# SAMD21_8X8_schematic.net
KiCad netlist of a schematic drawn in Altium Designer
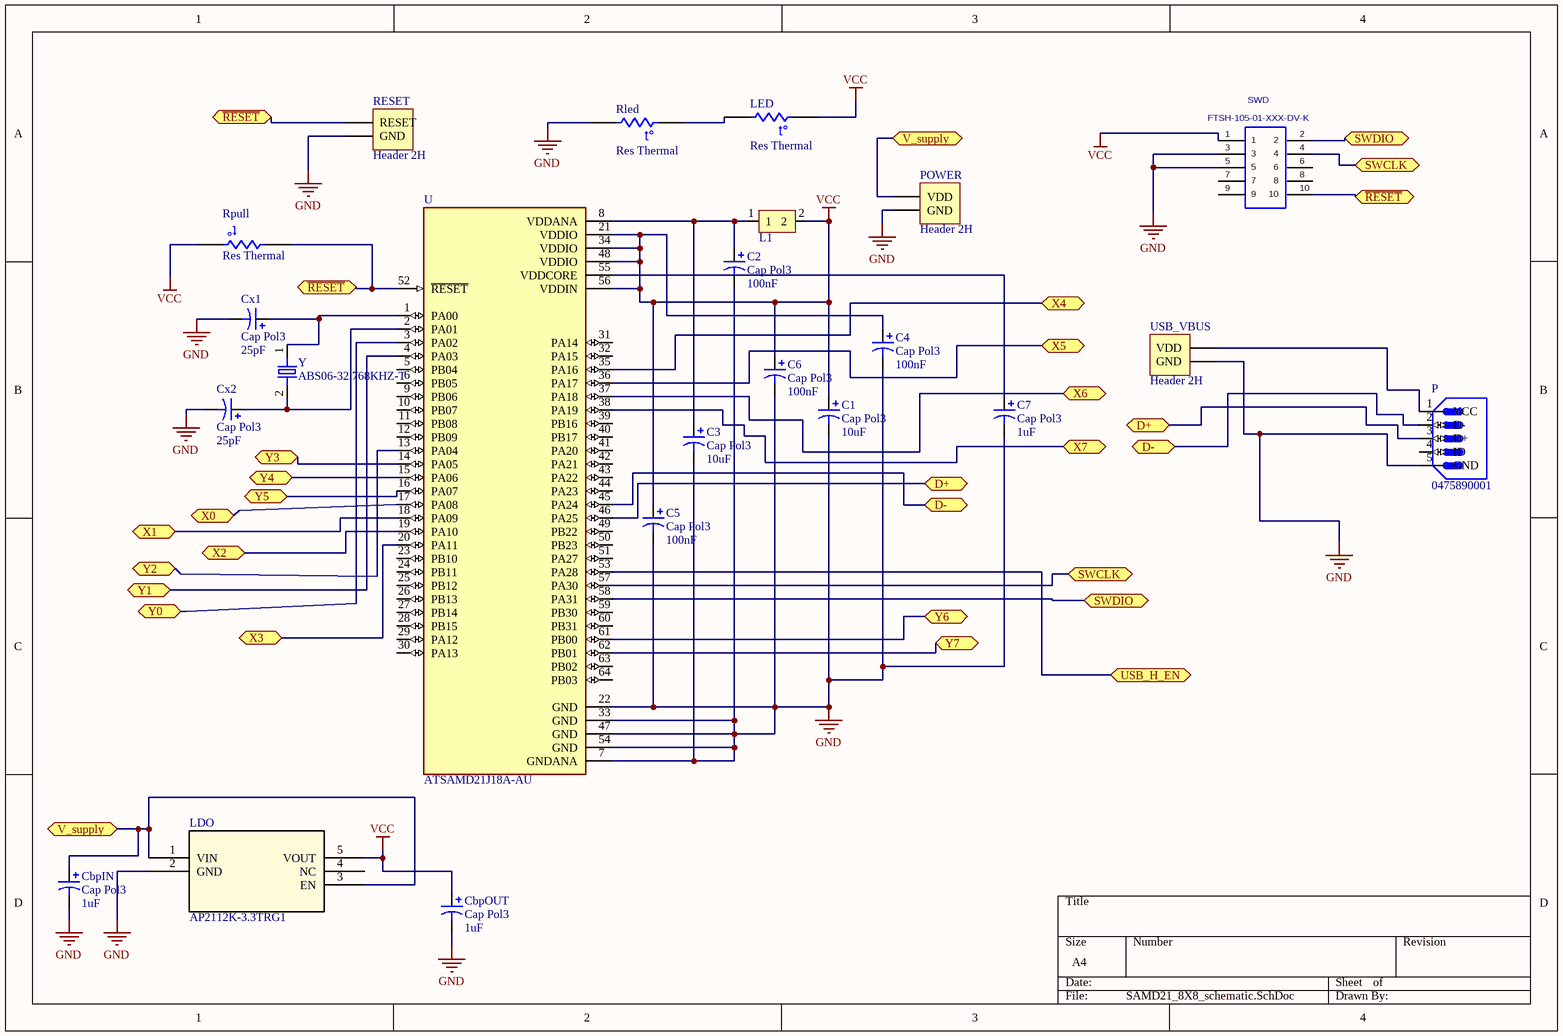
[diagram p0: SAMD21_8X8_schematic.SchDoc]

(export (version "E")
  (design (tool "Eeschema 10.0.6"))
  (components
    (comp (ref "C1")
      (value "Cap Pol3")
      (footprint "C0805")
      (description "Polarized Capacitor (Surface Mount)")
      (fields (field (name "ALTIUM_VALUE") "10uF") (field (name "PUBLISHER") "Altium Limited"))
      (libsource (lib "Miscellaneous Devices") (part "Cap Pol3"))
    )
    (comp (ref "C2")
      (value "Cap Pol3")
      (footprint "C0805")
      (description "Polarized Capacitor (Surface Mount)")
      (fields (field (name "ALTIUM_VALUE") "100nF") (field (name "PUBLISHER") "Altium Limited"))
      (libsource (lib "Miscellaneous Devices") (part "Cap Pol3"))
    )
    (comp (ref "C3")
      (value "Cap Pol3")
      (footprint "C0805")
      (description "Polarized Capacitor (Surface Mount)")
      (fields (field (name "ALTIUM_VALUE") "10uF") (field (name "PUBLISHER") "Altium Limited"))
      (libsource (lib "Miscellaneous Devices") (part "Cap Pol3"))
    )
    (comp (ref "C4")
      (value "Cap Pol3")
      (footprint "C0805")
      (description "Polarized Capacitor (Surface Mount)")
      (fields (field (name "ALTIUM_VALUE") "100nF") (field (name "PUBLISHER") "Altium Limited"))
      (libsource (lib "Miscellaneous Devices") (part "Cap Pol3"))
    )
    (comp (ref "C5")
      (value "Cap Pol3")
      (footprint "C0805")
      (description "Polarized Capacitor (Surface Mount)")
      (fields (field (name "ALTIUM_VALUE") "100nF") (field (name "PUBLISHER") "Altium Limited"))
      (libsource (lib "Miscellaneous Devices") (part "Cap Pol3"))
    )
    (comp (ref "C6")
      (value "Cap Pol3")
      (footprint "C0805")
      (description "Polarized Capacitor (Surface Mount)")
      (fields (field (name "ALTIUM_VALUE") "100nF") (field (name "PUBLISHER") "Altium Limited"))
      (libsource (lib "Miscellaneous Devices") (part "Cap Pol3"))
    )
    (comp (ref "C7")
      (value "Cap Pol3")
      (footprint "C0805")
      (description "Polarized Capacitor (Surface Mount)")
      (fields (field (name "ALTIUM_VALUE") "1uF") (field (name "PUBLISHER") "Altium Limited"))
      (libsource (lib "Miscellaneous Devices") (part "Cap Pol3"))
    )
    (comp (ref "CbpIN")
      (value "Cap Pol3")
      (footprint "C0805")
      (description "Polarized Capacitor (Surface Mount)")
      (fields (field (name "ALTIUM_VALUE") "1uF") (field (name "PUBLISHER") "Altium Limited"))
      (libsource (lib "Miscellaneous Devices") (part "Cap Pol3"))
    )
    (comp (ref "CbpOUT")
      (value "Cap Pol3")
      (footprint "C0805")
      (description "Polarized Capacitor (Surface Mount)")
      (fields (field (name "ALTIUM_VALUE") "1uF") (field (name "PUBLISHER") "Altium Limited"))
      (libsource (lib "Miscellaneous Devices") (part "Cap Pol3"))
    )
    (comp (ref "Cx1")
      (value "Cap Pol3")
      (footprint "C0805")
      (description "Polarized Capacitor (Surface Mount)")
      (fields (field (name "ALTIUM_VALUE") "25pF") (field (name "PUBLISHER") "Altium Limited"))
      (libsource (lib "Miscellaneous Devices") (part "Cap Pol3"))
    )
    (comp (ref "Cx2")
      (value "Cap Pol3")
      (footprint "C0805")
      (description "Polarized Capacitor (Surface Mount)")
      (fields (field (name "ALTIUM_VALUE") "25pF") (field (name "PUBLISHER") "Altium Limited"))
      (libsource (lib "Miscellaneous Devices") (part "Cap Pol3"))
    )
    (comp (ref "L1")
      (value "SRP4012TA-100M")
      (footprint "Inductor")
      (description "Inductor")
      (libsource (lib "SRP4012TA") (part "SRP4012TA-100M"))
    )
    (comp (ref "LDO")
      (value "AP2112K-3.3TRG1")
      (footprint "SOT_RG1_DIO")
      (description "No Description Available")
      (fields (field (name "COPYRIGHT") "Copyright (C) 2018 Accelerated Designs. All rights reserved"))
      (libsource (lib "2020-09-03_20-14-04") (part "AP2112K-3.3TRG1"))
    )
    (comp (ref "LED")
      (value "Res Thermal")
      (footprint "6-0805_N")
      (description "Thermistor")
      (fields (field (name "PUBLISHER") "Altium Limited"))
      (libsource (lib "Miscellaneous Devices") (part "Res Thermal"))
    )
    (comp (ref "P")
      (value "0475890001")
      (footprint "MOLEX_0475890001")
      (description "USB - micro AB Receptacle Connector 5 Position Surface Mount, Right Angle; Through Hole")
      (fields (field (name "DIGI-KEY_PART_NUMBER") "WM17143CT-ND") (field (name "MF") "Molex"))
      (libsource (lib "0475890001") (part "0475890001"))
    )
    (comp (ref "POWER")
      (value "Header 2H")
      (footprint "HDR1X2H")
      (description "Header, 2-Pin, Right Angle")
      (fields (field (name "PUBLISHER") "Altium Limited"))
      (libsource (lib "") (part "Header 2H_1"))
    )
    (comp (ref "RESET")
      (value "Header 2H")
      (footprint "HDR1X2H")
      (description "Header, 2-Pin, Right Angle")
      (fields (field (name "PUBLISHER") "Altium Limited"))
      (libsource (lib "") (part "Header 2H_1"))
    )
    (comp (ref "Rled")
      (value "Res Thermal")
      (footprint "6-0805_N")
      (description "Thermistor")
      (fields (field (name "PUBLISHER") "Altium Limited"))
      (libsource (lib "Miscellaneous Devices") (part "Res Thermal"))
    )
    (comp (ref "Rpull")
      (value "Res Thermal")
      (footprint "6-0805_N")
      (description "Thermistor")
      (fields (field (name "PUBLISHER") "Altium Limited"))
      (libsource (lib "Miscellaneous Devices") (part "Res Thermal"))
    )
    (comp (ref "SWD")
      (value "FTSH-105-01-XXX-DV-K")
      (footprint "FTSH-105-01-XXX-DV-K")
      (description "TERMINAL STRIP, .050\"(1.27mm) PITCH, 10 PINS, KEYED")
      (fields (field (name "MANUFACTURER") "SAMTEC") (field (name "CREATED") "November 30, 2016 - Wendy Xin"))
      (libsource (lib "FTSH-105-01-XXX-DV-K--Symbol-Altium-44987") (part "FTSH-105-01-XXX-DV-K"))
    )
    (comp (ref "U")
      (value "ATSAMD21J18A-AU")
      (footprint "QFP80P1600X1600X120-64N")
      (description "ARMÂ® CortexÂ®-M0+ SAM D21J Microcontroller IC 32-Bit 48MHz 256KB _256K x 8_ FLASH 64-TQFP _10x10_")
      (fields (field (name "MF") "Microchip"))
      (libsource (lib "ATSAMD21J18A-AU") (part "ATSAMD21J18A-AU"))
    )
    (comp (ref "USB_VBUS")
      (value "Header 2H")
      (footprint "HDR1X2H")
      (description "Header, 2-Pin, Right Angle")
      (fields (field (name "PUBLISHER") "Altium Limited"))
      (libsource (lib "Miscellaneous Connectors") (part "Header 2H"))
    )
    (comp (ref "Y")
      (value "ABS06-32.768KHZ-T")
      (footprint "XTAL_ABS06-32.768KHZ-T")
      (description "32.768kHz Â±20ppm Crystal 12.5pF 90 kOhms 2-SMD, No Lead")
      (fields (field (name "MF") "Abracon"))
      (libsource (lib "ABS06-32.768KHZ-T") (part "ABS06-32.768KHZ-T"))
    )
  )
  (nets
    (net (code "1") (name "/D+") (class "Default")
      (node (ref "P") (pin "3") (pinfunction "D+_3") (pintype "bidirectional"))
      (node (ref "U") (pin "46") (pinfunction "PA25_46") (pintype "bidirectional"))
    )
    (net (code "2") (name "/D-") (class "Default")
      (node (ref "P") (pin "2") (pinfunction "D-_2") (pintype "bidirectional"))
      (node (ref "U") (pin "45") (pinfunction "PA24_45") (pintype "bidirectional"))
    )
    (net (code "3") (name "/SWCLK") (class "Default")
      (node (ref "SWD") (pin "4") (pinfunction "4_4") (pintype "passive"))
      (node (ref "U") (pin "57") (pinfunction "PA30_57") (pintype "bidirectional"))
    )
    (net (code "4") (name "/SWDIO") (class "Default")
      (node (ref "SWD") (pin "2") (pinfunction "2_2") (pintype "passive"))
      (node (ref "U") (pin "58") (pinfunction "PA31_58") (pintype "bidirectional"))
    )
    (net (code "5") (name "/USB_H_EN") (class "Default")
      (node (ref "U") (pin "53") (pinfunction "PA28_53") (pintype "bidirectional"))
    )
    (net (code "6") (name "/V_supply") (class "Default")
      (node (ref "CbpIN") (pin "1") (pinfunction "1_1") (pintype "passive"))
      (node (ref "LDO") (pin "1") (pinfunction "VIN_1") (pintype "passive"))
      (node (ref "LDO") (pin "3") (pinfunction "EN_3") (pintype "passive"))
      (node (ref "POWER") (pin "1") (pinfunction "RESET_1") (pintype "passive"))
    )
    (net (code "7") (name "/X0") (class "Default")
      (node (ref "U") (pin "17") (pinfunction "PA08_17") (pintype "bidirectional"))
    )
    (net (code "8") (name "/X1") (class "Default")
      (node (ref "U") (pin "18") (pinfunction "PA09_18") (pintype "bidirectional"))
    )
    (net (code "9") (name "/X2") (class "Default")
      (node (ref "U") (pin "19") (pinfunction "PA10_19") (pintype "bidirectional"))
    )
    (net (code "10") (name "/X3") (class "Default")
      (node (ref "U") (pin "20") (pinfunction "PA11_20") (pintype "bidirectional"))
    )
    (net (code "11") (name "/X4") (class "Default")
      (node (ref "U") (pin "35") (pinfunction "PA16_35") (pintype "bidirectional"))
    )
    (net (code "12") (name "/X5") (class "Default")
      (node (ref "U") (pin "36") (pinfunction "PA17_36") (pintype "bidirectional"))
    )
    (net (code "13") (name "/X6") (class "Default")
      (node (ref "U") (pin "37") (pinfunction "PA18_37") (pintype "bidirectional"))
    )
    (net (code "14") (name "/X7") (class "Default")
      (node (ref "U") (pin "38") (pinfunction "PA19_38") (pintype "bidirectional"))
    )
    (net (code "15") (name "/Y0") (class "Default")
      (node (ref "U") (pin "3") (pinfunction "PA02_3") (pintype "bidirectional"))
    )
    (net (code "16") (name "/Y1") (class "Default")
      (node (ref "U") (pin "4") (pinfunction "PA03_4") (pintype "bidirectional"))
    )
    (net (code "17") (name "/Y2") (class "Default")
      (node (ref "U") (pin "13") (pinfunction "PA04_13") (pintype "bidirectional"))
    )
    (net (code "18") (name "/Y3") (class "Default")
      (node (ref "U") (pin "14") (pinfunction "PA05_14") (pintype "bidirectional"))
    )
    (net (code "19") (name "/Y4") (class "Default")
      (node (ref "U") (pin "15") (pinfunction "PA06_15") (pintype "bidirectional"))
    )
    (net (code "20") (name "/Y5") (class "Default")
      (node (ref "U") (pin "16") (pinfunction "PA07_16") (pintype "bidirectional"))
    )
    (net (code "21") (name "/Y6") (class "Default")
      (node (ref "U") (pin "61") (pinfunction "PB00_61") (pintype "bidirectional"))
    )
    (net (code "22") (name "/Y7") (class "Default")
      (node (ref "U") (pin "62") (pinfunction "PB01_62") (pintype "bidirectional"))
    )
    (net (code "23") (name "/~{RESET}") (class "Default")
      (node (ref "RESET") (pin "1") (pinfunction "RESET_1") (pintype "passive"))
      (node (ref "Rpull") (pin "2") (pinfunction "2_2") (pintype "passive"))
      (node (ref "SWD") (pin "10") (pinfunction "10_10") (pintype "passive"))
      (node (ref "U") (pin "52") (pinfunction "~{RESET}_52") (pintype "input"))
    )
    (net (code "24") (name "GND") (class "Default")
      (node (ref "C1") (pin "2") (pinfunction "2_2") (pintype "passive"))
      (node (ref "C2") (pin "2") (pinfunction "2_2") (pintype "passive"))
      (node (ref "C3") (pin "2") (pinfunction "2_2") (pintype "passive"))
      (node (ref "C4") (pin "2") (pinfunction "2_2") (pintype "passive"))
      (node (ref "C5") (pin "2") (pinfunction "2_2") (pintype "passive"))
      (node (ref "C6") (pin "2") (pinfunction "2_2") (pintype "passive"))
      (node (ref "C7") (pin "2") (pinfunction "2_2") (pintype "passive"))
      (node (ref "CbpIN") (pin "2") (pinfunction "2_2") (pintype "passive"))
      (node (ref "CbpOUT") (pin "2") (pinfunction "2_2") (pintype "passive"))
      (node (ref "Cx1") (pin "2") (pinfunction "2_2") (pintype "passive"))
      (node (ref "Cx2") (pin "2") (pinfunction "2_2") (pintype "passive"))
      (node (ref "LDO") (pin "2") (pinfunction "GND_2") (pintype "passive"))
      (node (ref "P") (pin "5") (pinfunction "GND_5") (pintype "power_in"))
      (node (ref "POWER") (pin "2") (pinfunction "GND_2") (pintype "passive"))
      (node (ref "RESET") (pin "2") (pinfunction "GND_2") (pintype "passive"))
      (node (ref "Rled") (pin "2") (pinfunction "2_2") (pintype "passive"))
      (node (ref "SWD") (pin "3") (pinfunction "3_3") (pintype "passive"))
      (node (ref "SWD") (pin "5") (pinfunction "5_5") (pintype "passive"))
      (node (ref "U") (pin "22") (pinfunction "GND_22") (pintype "power_in"))
      (node (ref "U") (pin "33") (pinfunction "GND_33") (pintype "power_in"))
      (node (ref "U") (pin "47") (pinfunction "GND_47") (pintype "power_in"))
      (node (ref "U") (pin "54") (pinfunction "GND_54") (pintype "power_in"))
      (node (ref "U") (pin "7") (pinfunction "GNDANA_7") (pintype "power_in"))
      (node (ref "USB_VBUS") (pin "1") (pinfunction "GND_1") (pintype "passive"))
    )
    (net (code "25") (name "Net-(LED-Pad2)") (class "Default")
      (node (ref "LED") (pin "2") (pinfunction "2_2") (pintype "passive"))
      (node (ref "Rled") (pin "1") (pinfunction "1_1") (pintype "passive"))
    )
    (net (code "26") (name "Net-(P-VCC)") (class "Default")
      (node (ref "P") (pin "1") (pinfunction "VCC_1") (pintype "power_in"))
      (node (ref "USB_VBUS") (pin "2") (pinfunction "VDD_2") (pintype "passive"))
    )
    (net (code "27") (name "Net-(U-PA00)") (class "Default")
      (node (ref "Cx1") (pin "1") (pinfunction "1_1") (pintype "passive"))
      (node (ref "U") (pin "1") (pinfunction "PA00_1") (pintype "bidirectional"))
      (node (ref "Y") (pin "1") (pinfunction "1_1") (pintype "passive"))
    )
    (net (code "28") (name "Net-(U-PA01)") (class "Default")
      (node (ref "Cx2") (pin "1") (pinfunction "1_1") (pintype "passive"))
      (node (ref "U") (pin "2") (pinfunction "PA01_2") (pintype "bidirectional"))
      (node (ref "Y") (pin "2") (pinfunction "2_2") (pintype "passive"))
    )
    (net (code "29") (name "Net-(U-VDDANA)") (class "Default")
      (node (ref "C2") (pin "1") (pinfunction "1_1") (pintype "passive"))
      (node (ref "C3") (pin "1") (pinfunction "1_1") (pintype "passive"))
      (node (ref "L1") (pin "1") (pinfunction "1_1") (pintype "passive"))
      (node (ref "U") (pin "8") (pinfunction "VDDANA_8") (pintype "power_in"))
    )
    (net (code "30") (name "Net-(U-VDDCORE)") (class "Default")
      (node (ref "C7") (pin "1") (pinfunction "1_1") (pintype "passive"))
      (node (ref "U") (pin "55") (pinfunction "VDDCORE_55") (pintype "power_in"))
    )
    (net (code "31") (name "VCC") (class "Default")
      (node (ref "C1") (pin "1") (pinfunction "1_1") (pintype "passive"))
      (node (ref "C4") (pin "1") (pinfunction "1_1") (pintype "passive"))
      (node (ref "C5") (pin "1") (pinfunction "1_1") (pintype "passive"))
      (node (ref "C6") (pin "1") (pinfunction "1_1") (pintype "passive"))
      (node (ref "CbpOUT") (pin "1") (pinfunction "1_1") (pintype "passive"))
      (node (ref "L1") (pin "2") (pinfunction "2_2") (pintype "passive"))
      (node (ref "LDO") (pin "5") (pinfunction "VOUT_5") (pintype "passive"))
      (node (ref "LED") (pin "1") (pinfunction "1_1") (pintype "passive"))
      (node (ref "Rpull") (pin "1") (pinfunction "1_1") (pintype "passive"))
      (node (ref "SWD") (pin "1") (pinfunction "1_1") (pintype "passive"))
      (node (ref "U") (pin "21") (pinfunction "VDDIO_21") (pintype "power_in"))
      (node (ref "U") (pin "34") (pinfunction "VDDIO_34") (pintype "power_in"))
      (node (ref "U") (pin "48") (pinfunction "VDDIO_48") (pintype "power_in"))
      (node (ref "U") (pin "56") (pinfunction "VDDIN_56") (pintype "power_in"))
    )
    (net (code "32") (name "unconnected-(LDO-NC-Pad4)") (class "Default")
      (node (ref "LDO") (pin "4") (pinfunction "NC_4") (pintype "passive"))
    )
    (net (code "33") (name "unconnected-(P-ID-Pad4)") (class "Default")
      (node (ref "P") (pin "4") (pinfunction "ID_4") (pintype "bidirectional"))
    )
    (net (code "34") (name "unconnected-(SWD-Pad6)") (class "Default")
      (node (ref "SWD") (pin "6") (pinfunction "6_6") (pintype "passive"))
    )
    (net (code "35") (name "unconnected-(SWD-Pad7)") (class "Default")
      (node (ref "SWD") (pin "7") (pinfunction "7_7") (pintype "passive"))
    )
    (net (code "36") (name "unconnected-(SWD-Pad8)") (class "Default")
      (node (ref "SWD") (pin "8") (pinfunction "8_8") (pintype "passive"))
    )
    (net (code "37") (name "unconnected-(SWD-Pad9)") (class "Default")
      (node (ref "SWD") (pin "9") (pinfunction "9_9") (pintype "passive"))
    )
    (net (code "38") (name "unconnected-(U-PA12-Pad29)") (class "Default")
      (node (ref "U") (pin "29") (pinfunction "PA12_29") (pintype "bidirectional"))
    )
    (net (code "39") (name "unconnected-(U-PA13-Pad30)") (class "Default")
      (node (ref "U") (pin "30") (pinfunction "PA13_30") (pintype "bidirectional"))
    )
    (net (code "40") (name "unconnected-(U-PA14-Pad31)") (class "Default")
      (node (ref "U") (pin "31") (pinfunction "PA14_31") (pintype "bidirectional"))
    )
    (net (code "41") (name "unconnected-(U-PA15-Pad32)") (class "Default")
      (node (ref "U") (pin "32") (pinfunction "PA15_32") (pintype "bidirectional"))
    )
    (net (code "42") (name "unconnected-(U-PA20-Pad41)") (class "Default")
      (node (ref "U") (pin "41") (pinfunction "PA20_41") (pintype "bidirectional"))
    )
    (net (code "43") (name "unconnected-(U-PA21-Pad42)") (class "Default")
      (node (ref "U") (pin "42") (pinfunction "PA21_42") (pintype "bidirectional"))
    )
    (net (code "44") (name "unconnected-(U-PA22-Pad43)") (class "Default")
      (node (ref "U") (pin "43") (pinfunction "PA22_43") (pintype "bidirectional"))
    )
    (net (code "45") (name "unconnected-(U-PA23-Pad44)") (class "Default")
      (node (ref "U") (pin "44") (pinfunction "PA23_44") (pintype "bidirectional"))
    )
    (net (code "46") (name "unconnected-(U-PA27-Pad51)") (class "Default")
      (node (ref "U") (pin "51") (pinfunction "PA27_51") (pintype "bidirectional"))
    )
    (net (code "47") (name "unconnected-(U-PB02-Pad63)") (class "Default")
      (node (ref "U") (pin "63") (pinfunction "PB02_63") (pintype "bidirectional"))
    )
    (net (code "48") (name "unconnected-(U-PB03-Pad64)") (class "Default")
      (node (ref "U") (pin "64") (pinfunction "PB03_64") (pintype "bidirectional"))
    )
    (net (code "49") (name "unconnected-(U-PB04-Pad5)") (class "Default")
      (node (ref "U") (pin "5") (pinfunction "PB04_5") (pintype "bidirectional"))
    )
    (net (code "50") (name "unconnected-(U-PB05-Pad6)") (class "Default")
      (node (ref "U") (pin "6") (pinfunction "PB05_6") (pintype "bidirectional"))
    )
    (net (code "51") (name "unconnected-(U-PB06-Pad9)") (class "Default")
      (node (ref "U") (pin "9") (pinfunction "PB06_9") (pintype "bidirectional"))
    )
    (net (code "52") (name "unconnected-(U-PB07-Pad10)") (class "Default")
      (node (ref "U") (pin "10") (pinfunction "PB07_10") (pintype "bidirectional"))
    )
    (net (code "53") (name "unconnected-(U-PB08-Pad11)") (class "Default")
      (node (ref "U") (pin "11") (pinfunction "PB08_11") (pintype "bidirectional"))
    )
    (net (code "54") (name "unconnected-(U-PB09-Pad12)") (class "Default")
      (node (ref "U") (pin "12") (pinfunction "PB09_12") (pintype "bidirectional"))
    )
    (net (code "55") (name "unconnected-(U-PB10-Pad23)") (class "Default")
      (node (ref "U") (pin "23") (pinfunction "PB10_23") (pintype "bidirectional"))
    )
    (net (code "56") (name "unconnected-(U-PB11-Pad24)") (class "Default")
      (node (ref "U") (pin "24") (pinfunction "PB11_24") (pintype "bidirectional"))
    )
    (net (code "57") (name "unconnected-(U-PB12-Pad25)") (class "Default")
      (node (ref "U") (pin "25") (pinfunction "PB12_25") (pintype "bidirectional"))
    )
    (net (code "58") (name "unconnected-(U-PB13-Pad26)") (class "Default")
      (node (ref "U") (pin "26") (pinfunction "PB13_26") (pintype "bidirectional"))
    )
    (net (code "59") (name "unconnected-(U-PB14-Pad27)") (class "Default")
      (node (ref "U") (pin "27") (pinfunction "PB14_27") (pintype "bidirectional"))
    )
    (net (code "60") (name "unconnected-(U-PB15-Pad28)") (class "Default")
      (node (ref "U") (pin "28") (pinfunction "PB15_28") (pintype "bidirectional"))
    )
    (net (code "61") (name "unconnected-(U-PB16-Pad39)") (class "Default")
      (node (ref "U") (pin "39") (pinfunction "PB16_39") (pintype "bidirectional"))
    )
    (net (code "62") (name "unconnected-(U-PB17-Pad40)") (class "Default")
      (node (ref "U") (pin "40") (pinfunction "PB17_40") (pintype "bidirectional"))
    )
    (net (code "63") (name "unconnected-(U-PB22-Pad49)") (class "Default")
      (node (ref "U") (pin "49") (pinfunction "PB22_49") (pintype "bidirectional"))
    )
    (net (code "64") (name "unconnected-(U-PB23-Pad50)") (class "Default")
      (node (ref "U") (pin "50") (pinfunction "PB23_50") (pintype "bidirectional"))
    )
    (net (code "65") (name "unconnected-(U-PB30-Pad59)") (class "Default")
      (node (ref "U") (pin "59") (pinfunction "PB30_59") (pintype "bidirectional"))
    )
    (net (code "66") (name "unconnected-(U-PB31-Pad60)") (class "Default")
      (node (ref "U") (pin "60") (pinfunction "PB31_60") (pintype "bidirectional"))
    )
  )
)
